# Base02.net
KiCad netlist of a schematic drawn in Altium Designer
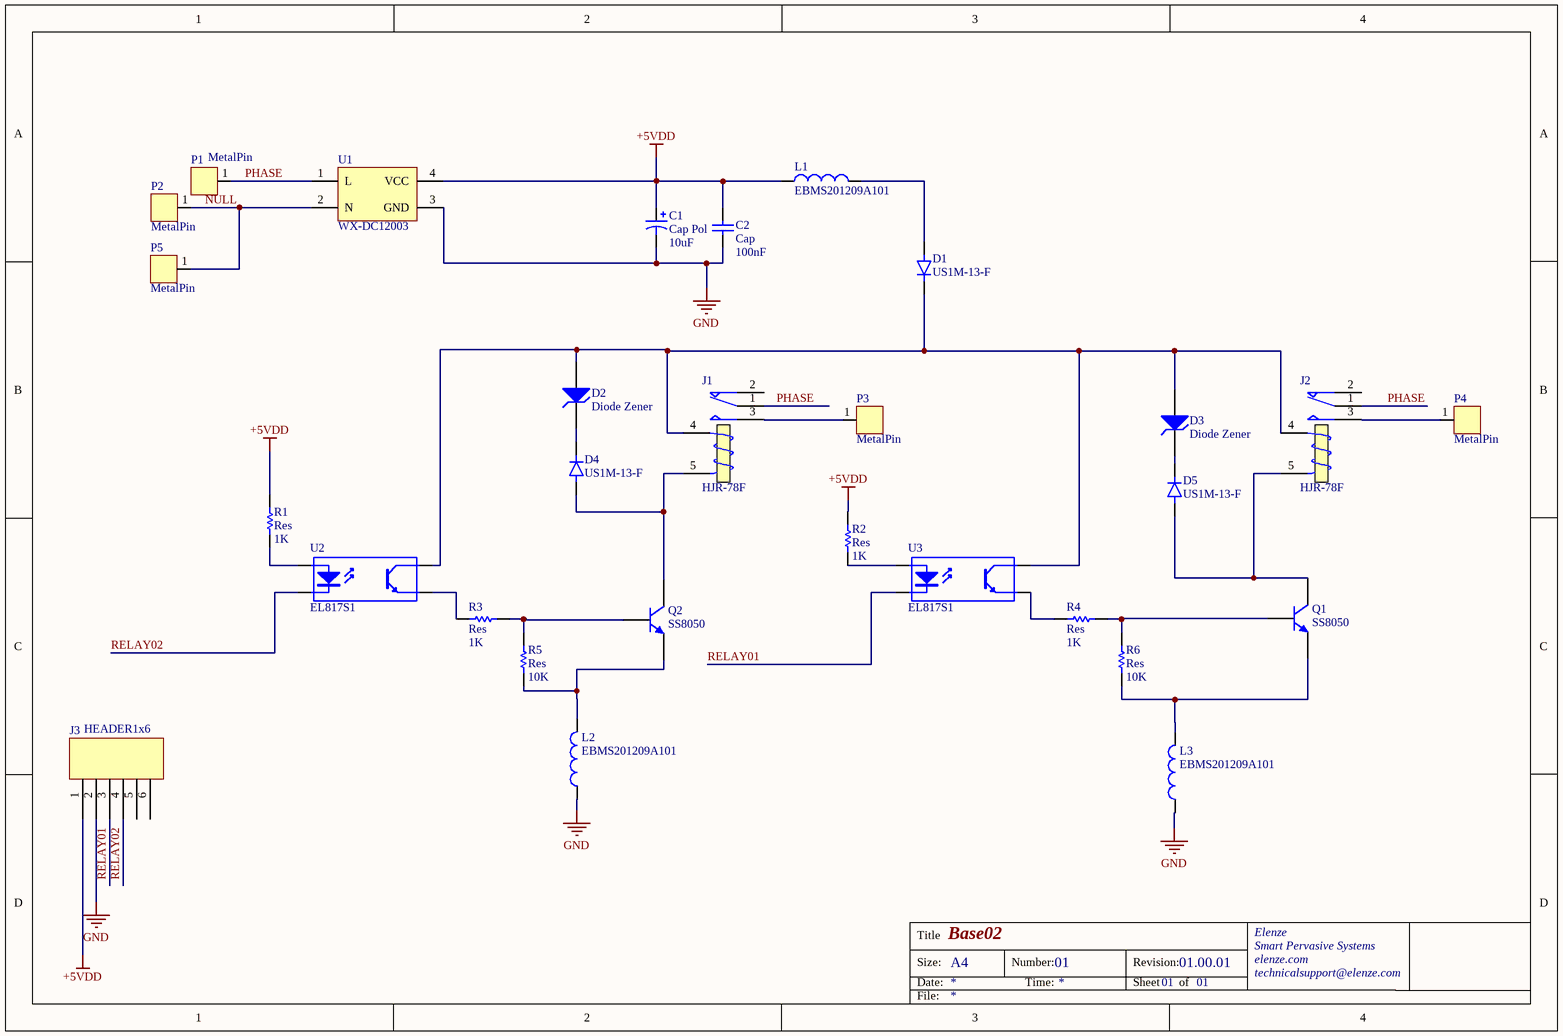
[diagram p0: Base02.SchDoc]

(export (version "E")
  (design (tool "Eeschema 10.0.6"))
  (components
    (comp (ref "C1")
      (value "Cap Pol")
      (footprint "EL_C_4_5")
      (description "Polarized Capacitor (Axial)")
      (fields (field (name "ALTIUM_VALUE") "10uF") (field (name "PUBLISHER") "Altium Limited"))
      (libsource (lib "Elenze") (part "Cap Pol"))
    )
    (comp (ref "C2")
      (value "Cap")
      (footprint "0402")
      (description "Capacitor")
      (fields (field (name "ALTIUM_VALUE") "100nF") (field (name "PUBLISHER") "Altium Limited"))
      (libsource (lib "Elenze") (part "Cap"))
    )
    (comp (ref "D1")
      (value "US1M-13-F")
      (footprint "DIO_ES1J")
      (description "Diode Standard 1000V 1A Surface Mount SMA")
      (fields (field (name "MF") "Diodes Inc."))
      (libsource (lib "Elenze") (part "US1M-13-F"))
    )
    (comp (ref "D2")
      (value "Diode Zener")
      (footprint "DO1206")
      (description "Zener Diode")
      (fields (field (name "PUBLISHER") "Altium Limited"))
      (libsource (lib "Elenze") (part "Diode Zener"))
    )
    (comp (ref "D3")
      (value "Diode Zener")
      (footprint "DO1206")
      (description "Zener Diode")
      (fields (field (name "PUBLISHER") "Altium Limited"))
      (libsource (lib "Elenze") (part "Diode Zener"))
    )
    (comp (ref "D4")
      (value "US1M-13-F")
      (footprint "DIO_ES1J")
      (description "Diode Standard 1000V 1A Surface Mount SMA")
      (fields (field (name "MF") "Diodes Inc."))
      (libsource (lib "Elenze") (part "US1M-13-F"))
    )
    (comp (ref "D5")
      (value "US1M-13-F")
      (footprint "DIO_ES1J")
      (description "Diode Standard 1000V 1A Surface Mount SMA")
      (fields (field (name "MF") "Diodes Inc."))
      (libsource (lib "Elenze") (part "US1M-13-F"))
    )
    (comp (ref "J1")
      (value "HJR-78F")
      (footprint "RELAY")
      (description "20A switching capability Small size auto Relay")
      (fields (field (name "PART NUMBER") "TRKM S-Z") (field (name "MANUFACTURER") "Tianbo"))
      (libsource (lib "Elenze") (part "HJR-78F"))
    )
    (comp (ref "J2")
      (value "HJR-78F")
      (footprint "RELAY")
      (description "20A switching capability Small size auto Relay")
      (fields (field (name "PART NUMBER") "TRKM S-Z") (field (name "MANUFACTURER") "Tianbo"))
      (libsource (lib "Elenze") (part "HJR-78F"))
    )
    (comp (ref "J3")
      (value "HEADER1x6")
      (footprint "M-Header 6")
      (description "HEADER 1x6")
      (libsource (lib "Elenze") (part "HEADER1x6"))
    )
    (comp (ref "L1")
      (value "EBMS201209A101")
      (footprint "IND0805")
      (description "INDUCTOR SMD")
      (libsource (lib "Inactive components") (part "INDUCTOR SMD"))
    )
    (comp (ref "L2")
      (value "EBMS201209A101")
      (footprint "IND0805")
      (description "INDUCTOR SMD")
      (libsource (lib "Inactive components") (part "INDUCTOR SMD"))
    )
    (comp (ref "L3")
      (value "EBMS201209A101")
      (footprint "IND0805")
      (description "INDUCTOR SMD")
      (libsource (lib "Inactive components") (part "INDUCTOR SMD"))
    )
    (comp (ref "P1") (value "MetalPin") (footprint "MetalPin") (libsource (lib "Elenze") (part "MetalPin")))
    (comp (ref "P2") (value "MetalPin") (footprint "MetalPin") (libsource (lib "Elenze") (part "MetalPin")))
    (comp (ref "P3") (value "MetalPin") (footprint "MetalPin") (libsource (lib "") (part "MetalPin_1")))
    (comp (ref "P4") (value "MetalPin") (footprint "MetalPin") (libsource (lib "") (part "MetalPin_1")))
    (comp (ref "P5") (value "MetalPin") (footprint "MetalPin") (libsource (lib "Elenze") (part "MetalPin")))
    (comp (ref "Q1")
      (value "SS8050")
      (footprint "SOT-23")
      (description "NPN General Purpose Amplifier")
      (fields (field (name "PUBLISHER") "Altium Limited"))
      (libsource (lib "Elenze") (part "SS8050"))
    )
    (comp (ref "Q2")
      (value "SS8050")
      (footprint "SOT-23")
      (description "NPN General Purpose Amplifier")
      (fields (field (name "PUBLISHER") "Altium Limited"))
      (libsource (lib "Elenze") (part "SS8050"))
    )
    (comp (ref "R1")
      (value "Res")
      (footprint "0402")
      (description "Resistor")
      (fields (field (name "ALTIUM_VALUE") "1K") (field (name "PUBLISHER") "Altium Limited"))
      (libsource (lib "Elenze") (part "Res"))
    )
    (comp (ref "R2")
      (value "Res")
      (footprint "0402")
      (description "Resistor")
      (fields (field (name "ALTIUM_VALUE") "1K") (field (name "PUBLISHER") "Altium Limited"))
      (libsource (lib "Elenze") (part "Res"))
    )
    (comp (ref "R3")
      (value "Res")
      (footprint "0402")
      (description "Resistor")
      (fields (field (name "ALTIUM_VALUE") "1K") (field (name "PUBLISHER") "Altium Limited"))
      (libsource (lib "Elenze") (part "Res"))
    )
    (comp (ref "R4")
      (value "Res")
      (footprint "0402")
      (description "Resistor")
      (fields (field (name "ALTIUM_VALUE") "1K") (field (name "PUBLISHER") "Altium Limited"))
      (libsource (lib "Elenze") (part "Res"))
    )
    (comp (ref "R5")
      (value "Res")
      (footprint "0402")
      (description "Resistor")
      (fields (field (name "ALTIUM_VALUE") "10K") (field (name "PUBLISHER") "Altium Limited"))
      (libsource (lib "Elenze") (part "Res"))
    )
    (comp (ref "R6")
      (value "Res")
      (footprint "0402")
      (description "Resistor")
      (fields (field (name "ALTIUM_VALUE") "10K") (field (name "PUBLISHER") "Altium Limited"))
      (libsource (lib "Elenze") (part "Res"))
    )
    (comp (ref "U1")
      (value "WX-DC12003")
      (footprint "WX-DC12003")
      (description "85~265V AC to 5V 3.5W DC Isolated Power Supply Module")
      (fields (field (name "MANUFACTURER") "Aerial telecommunications"))
      (libsource (lib "Elenze") (part "WX-DC12003"))
    )
    (comp (ref "U2")
      (value "EL817S1")
      (footprint "SOIC254P1030X390-4N_EL817(S1)(A)(TU)-VG")
      (description "4 PIN DIP Phototransistor Photocoupler")
      (fields (field (name "MANUFACTURER") "Everlight"))
      (libsource (lib "Elenze") (part "EL817S1"))
    )
    (comp (ref "U3")
      (value "EL817S1")
      (footprint "SOIC254P1030X390-4N_EL817(S1)(A)(TU)-VG")
      (description "4 PIN DIP Phototransistor Photocoupler")
      (fields (field (name "MANUFACTURER") "Everlight"))
      (libsource (lib "Elenze") (part "EL817S1"))
    )
  )
  (nets
    (net (code "1") (name "+5VDD") (class "Default")
      (node (ref "C1") (pin "1") (pinfunction "1_1") (pintype "passive"))
      (node (ref "C2") (pin "2") (pinfunction "2_2") (pintype "passive"))
      (node (ref "J3") (pin "1") (pinfunction "1_1") (pintype "passive"))
      (node (ref "L1") (pin "1") (pinfunction "1_1") (pintype "passive"))
      (node (ref "R1") (pin "1") (pinfunction "1_1") (pintype "passive"))
      (node (ref "R2") (pin "1") (pinfunction "1_1") (pintype "passive"))
      (node (ref "U1") (pin "4") (pinfunction "VCC_4") (pintype "passive"))
    )
    (net (code "2") (name "/NULL") (class "Default")
      (node (ref "P2") (pin "1") (pinfunction "1_1") (pintype "passive"))
      (node (ref "P5") (pin "1") (pinfunction "1_1") (pintype "passive"))
      (node (ref "U1") (pin "2") (pinfunction "N_2") (pintype "passive"))
    )
    (net (code "3") (name "/PHASE") (class "Default")
      (node (ref "J1") (pin "1") (pinfunction "COM_1") (pintype "passive"))
      (node (ref "J2") (pin "1") (pinfunction "COM_1") (pintype "passive"))
      (node (ref "P1") (pin "1") (pinfunction "1_1") (pintype "passive"))
      (node (ref "U1") (pin "1") (pinfunction "L_1") (pintype "passive"))
    )
    (net (code "4") (name "/RELAY01") (class "Default")
      (node (ref "J3") (pin "3") (pinfunction "3_3") (pintype "passive"))
      (node (ref "U3") (pin "2") (pinfunction "K_2") (pintype "power_in"))
    )
    (net (code "5") (name "/RELAY02") (class "Default")
      (node (ref "J3") (pin "4") (pinfunction "4_4") (pintype "passive"))
      (node (ref "U2") (pin "2") (pinfunction "K_2") (pintype "power_in"))
    )
    (net (code "6") (name "GND") (class "Default")
      (node (ref "C1") (pin "2") (pinfunction "2_2") (pintype "passive"))
      (node (ref "C2") (pin "1") (pinfunction "1_1") (pintype "passive"))
      (node (ref "J3") (pin "2") (pinfunction "2_2") (pintype "passive"))
      (node (ref "L2") (pin "1") (pinfunction "1_1") (pintype "passive"))
      (node (ref "L3") (pin "1") (pinfunction "1_1") (pintype "passive"))
      (node (ref "U1") (pin "3") (pinfunction "GND_3") (pintype "passive"))
    )
    (net (code "7") (name "Net-(D1-PadA)") (class "Default")
      (node (ref "D1") (pin "A") (pinfunction "A_A") (pintype "passive"))
      (node (ref "L1") (pin "2") (pinfunction "2_2") (pintype "passive"))
    )
    (net (code "8") (name "Net-(D2-A)") (class "Default")
      (node (ref "D1") (pin "K") (pinfunction "K_K") (pintype "passive"))
      (node (ref "D2") (pin "1") (pinfunction "A_1") (pintype "passive"))
      (node (ref "D3") (pin "1") (pinfunction "A_1") (pintype "passive"))
      (node (ref "J1") (pin "4") (pinfunction "T1_4") (pintype "passive"))
      (node (ref "J2") (pin "4") (pinfunction "T1_4") (pintype "passive"))
      (node (ref "U2") (pin "4") (pinfunction "C_4") (pintype "power_in"))
      (node (ref "U3") (pin "4") (pinfunction "C_4") (pintype "power_in"))
    )
    (net (code "9") (name "Net-(D2-K)") (class "Default")
      (node (ref "D2") (pin "2") (pinfunction "K_2") (pintype "passive"))
      (node (ref "D4") (pin "K") (pinfunction "K_K") (pintype "passive"))
    )
    (net (code "10") (name "Net-(D3-K)") (class "Default")
      (node (ref "D3") (pin "2") (pinfunction "K_2") (pintype "passive"))
      (node (ref "D5") (pin "K") (pinfunction "K_K") (pintype "passive"))
    )
    (net (code "11") (name "Net-(J1-NO)") (class "Default")
      (node (ref "J1") (pin "3") (pinfunction "NO_3") (pintype "passive"))
      (node (ref "P3") (pin "1") (pinfunction "1_1") (pintype "passive"))
    )
    (net (code "12") (name "Net-(J1-T2)") (class "Default")
      (node (ref "D4") (pin "A") (pinfunction "A_A") (pintype "passive"))
      (node (ref "J1") (pin "5") (pinfunction "T2_5") (pintype "passive"))
      (node (ref "Q2") (pin "3") (pinfunction "C_3") (pintype "passive"))
    )
    (net (code "13") (name "Net-(J2-NO)") (class "Default")
      (node (ref "J2") (pin "3") (pinfunction "NO_3") (pintype "passive"))
      (node (ref "P4") (pin "1") (pinfunction "1_1") (pintype "passive"))
    )
    (net (code "14") (name "Net-(J2-T2)") (class "Default")
      (node (ref "D5") (pin "A") (pinfunction "A_A") (pintype "passive"))
      (node (ref "J2") (pin "5") (pinfunction "T2_5") (pintype "passive"))
      (node (ref "Q1") (pin "3") (pinfunction "C_3") (pintype "passive"))
    )
    (net (code "15") (name "Net-(Q1-B)") (class "Default")
      (node (ref "Q1") (pin "1") (pinfunction "B_1") (pintype "passive"))
      (node (ref "R4") (pin "2") (pinfunction "2_2") (pintype "passive"))
      (node (ref "R6") (pin "2") (pinfunction "2_2") (pintype "passive"))
    )
    (net (code "16") (name "Net-(Q1-E)") (class "Default")
      (node (ref "L3") (pin "2") (pinfunction "2_2") (pintype "passive"))
      (node (ref "Q1") (pin "2") (pinfunction "E_2") (pintype "passive"))
      (node (ref "R6") (pin "1") (pinfunction "1_1") (pintype "passive"))
    )
    (net (code "17") (name "Net-(Q2-B)") (class "Default")
      (node (ref "Q2") (pin "1") (pinfunction "B_1") (pintype "passive"))
      (node (ref "R3") (pin "2") (pinfunction "2_2") (pintype "passive"))
      (node (ref "R5") (pin "2") (pinfunction "2_2") (pintype "passive"))
    )
    (net (code "18") (name "Net-(Q2-E)") (class "Default")
      (node (ref "L2") (pin "2") (pinfunction "2_2") (pintype "passive"))
      (node (ref "Q2") (pin "2") (pinfunction "E_2") (pintype "passive"))
      (node (ref "R5") (pin "1") (pinfunction "1_1") (pintype "passive"))
    )
    (net (code "19") (name "Net-(U2-A)") (class "Default")
      (node (ref "R1") (pin "2") (pinfunction "2_2") (pintype "passive"))
      (node (ref "U2") (pin "1") (pinfunction "A_1") (pintype "power_in"))
    )
    (net (code "20") (name "Net-(U2-E)") (class "Default")
      (node (ref "R3") (pin "1") (pinfunction "1_1") (pintype "passive"))
      (node (ref "U2") (pin "3") (pinfunction "E_3") (pintype "power_in"))
    )
    (net (code "21") (name "Net-(U3-A)") (class "Default")
      (node (ref "R2") (pin "2") (pinfunction "2_2") (pintype "passive"))
      (node (ref "U3") (pin "1") (pinfunction "A_1") (pintype "power_in"))
    )
    (net (code "22") (name "Net-(U3-E)") (class "Default")
      (node (ref "R4") (pin "1") (pinfunction "1_1") (pintype "passive"))
      (node (ref "U3") (pin "3") (pinfunction "E_3") (pintype "power_in"))
    )
    (net (code "23") (name "unconnected-(J1-NC-Pad2)") (class "Default")
      (node (ref "J1") (pin "2") (pinfunction "NC_2") (pintype "passive"))
    )
    (net (code "24") (name "unconnected-(J2-NC-Pad2)") (class "Default")
      (node (ref "J2") (pin "2") (pinfunction "NC_2") (pintype "passive"))
    )
    (net (code "25") (name "unconnected-(J3-Pad5)") (class "Default")
      (node (ref "J3") (pin "5") (pinfunction "5_5") (pintype "passive"))
    )
    (net (code "26") (name "unconnected-(J3-Pad6)") (class "Default")
      (node (ref "J3") (pin "6") (pinfunction "6_6") (pintype "passive"))
    )
  )
)
